# Buck.net
KiCad netlist of a schematic drawn in Altium Designer
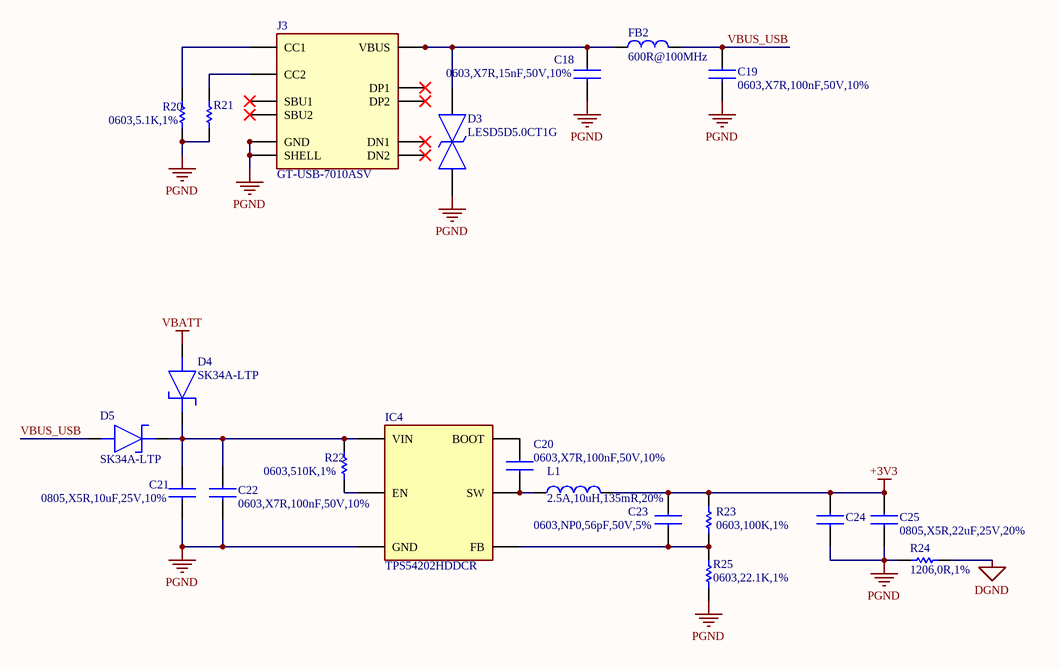
[diagram p0: Buck.SchDoc]

(export (version "E")
  (design (tool "Eeschema 10.0.6"))
  (components
    (comp (ref "C18")
      (value "0603,X7R,15nF,50V,10%")
      (footprint "CAPC1608X90N")
      (description "50V 15nF X7R ±10% 0603 Multilayer Ceramic Capacitors MLCC - SMD/SMT ROHS")
      (fields
        (field (name "MANUFACTURER_PART_NUMBER") "CC0603KRX7R9BB153")
        (field (name "MOUSER PART NUMBER") "603-CC603KRX7R9BB104")
      )
      (libsource (lib "ESC") (part "CC0603KRX7R9BB153"))
    )
    (comp (ref "C19")
      (value "0603,X7R,100nF,50V,10%")
      (footprint "CAPC1608X90N")
      (description "50V 100nF X7R ±10% 0603 Multilayer Ceramic Capacitors MLCC - SMD/SMT ROHS")
      (fields
        (field (name "MANUFACTURER_PART_NUMBER") "CC0603KRX7R9BB104")
        (field (name "MOUSER PART NUMBER") "603-CC603KRX7R9BB104")
      )
      (libsource (lib "ESC") (part "CC0603KRX7R9BB104"))
    )
    (comp (ref "C20")
      (value "0603,X7R,100nF,50V,10%")
      (footprint "CAPC1608X90N")
      (description "50V 100nF X7R ±10% 0603 Multilayer Ceramic Capacitors MLCC - SMD/SMT ROHS")
      (fields
        (field (name "MANUFACTURER_PART_NUMBER") "CC0603KRX7R9BB104")
        (field (name "MOUSER PART NUMBER") "603-CC603KRX7R9BB104")
      )
      (libsource (lib "ESC") (part "CC0603KRX7R9BB104"))
    )
    (comp (ref "C21")
      (value "0805,X5R,10uF,25V,10%")
      (footprint "CAPC2012X145N")
      (description "10 µF ±10% 25V Ceramic Capacitor X5R 0805 (2012 Metric)")
      (fields
        (field (name "MANUFACTURER_PART_NUMBER") "CC0805KKX5R8BB106")
        (field (name "MOUSER PART NUMBER") "603-CC805KKX5R8BB106")
      )
      (libsource (lib "ESC") (part "CC0805KKX5R8BB106"))
    )
    (comp (ref "C22")
      (value "0603,X7R,100nF,50V,10%")
      (footprint "CAPC1608X90N")
      (description "50V 100nF X7R ±10% 0603 Multilayer Ceramic Capacitors MLCC - SMD/SMT ROHS")
      (fields
        (field (name "MANUFACTURER_PART_NUMBER") "CC0603KRX7R9BB104")
        (field (name "MOUSER PART NUMBER") "603-CC603KRX7R9BB104")
      )
      (libsource (lib "ESC") (part "CC0603KRX7R9BB104"))
    )
    (comp (ref "C23")
      (value "0603,NP0,56pF,50V,5%")
      (footprint "CAPC1608X90N")
      (description "50V 56pF NP0 ±5% 0603 Ceramic Capacitors RoHS")
      (fields
        (field (name "MANUFACTURER_PART_NUMBER") "CC0603JRNPO9BN560")
        (field (name "MOUSER PART NUMBER") "603-CC603KRX7R9BB105")
      )
      (libsource (lib "ESC") (part "CC0603JRNPO9BN560"))
    )
    (comp (ref "C24")
      (value "0805,X5R,22uF,25V,20%")
      (footprint "CAPC2012X145N")
      (description "25V 22uF X5R ±20% 0805 Ceramic Capacitors RoHS")
      (fields
        (field (name "MANUFACTURER_PART_NUMBER") "CC0805MKX5R8BB226")
        (field (name "MOUSER PART NUMBER") "603-CC805KKX5R8BB106")
      )
      (libsource (lib "ESC") (part "CC0805MKX5R8BB226"))
    )
    (comp (ref "C25")
      (value "0805,X5R,22uF,25V,20%")
      (footprint "CAPC2012X145N")
      (description "25V 22uF X5R ±20% 0805 Ceramic Capacitors RoHS")
      (fields
        (field (name "MANUFACTURER_PART_NUMBER") "CC0805MKX5R8BB226")
        (field (name "MOUSER PART NUMBER") "603-CC805KKX5R8BB106")
      )
      (libsource (lib "ESC") (part "CC0805MKX5R8BB226"))
    )
    (comp (ref "D3")
      (value "LESD5D5.0CT1G")
      (footprint "LESD5D50CT1G")
      (description "9.4A 18.6V 5.6V Bidirectional 5V SOD-523 ESD and Surge Protection (TVS/ESD) ROHS")
      (fields (field (name "LCSC PART #") "C383211"))
      (libsource (lib "ESC") (part "LESD5D5.0CT1G"))
    )
    (comp (ref "D4")
      (value "SK34A-LTP")
      (footprint "SK34ALTP")
      (description "80A 40V 500mV@3A 3A SMA(DO-214AC) Single Diodes RoHS")
      (fields (field (name "MOUSER PART NUMBER") "833-SK34A-LTP") (field (name "LCSC PART #") "C85269"))
      (libsource (lib "ESC") (part "SK34A-LTP"))
    )
    (comp (ref "D5")
      (value "SK34A-LTP")
      (footprint "SK34ALTP")
      (description "80A 40V 500mV@3A 3A SMA(DO-214AC) Single Diodes RoHS")
      (fields (field (name "MOUSER PART NUMBER") "833-SK34A-LTP") (field (name "LCSC PART #") "C85269"))
      (libsource (lib "ESC") (part "SK34A-LTP"))
    )
    (comp (ref "FB2")
      (value "600R@100MHz")
      (footprint "L0603")
      (description "380mΩ ±25% 600Ω@100MHz 0603 Ferrite Beads ROHS")
      (fields (field (name "LCSC PART #") "C19330"))
      (libsource (lib "ESC") (part "BLM18AG601SN1D"))
    )
    (comp (ref "IC4")
      (value "TPS54202HDDCR")
      (footprint "SOT95P280X100-6N")
      (fields (field (name "MOUSER PART NUMBER") "595-TPS54202HDDCR") (field (name "LCSC PART #") "C527684"))
      (libsource (lib "ESC") (part "TPS54202HDDCR"))
    )
    (comp (ref "J3")
      (value "GT-USB-7010ASV")
      (footprint "USB-C-SMD_G-SWITCH_GT-USB-7010ASV")
      (description "USB 2.0 3A 1 Surface Mount, Right Angle 16P Female -40℃~+85℃ Type-C SMD USB Connectors ROHS")
      (fields (field (name "LCSC PART #") "C2988369"))
      (libsource (lib "ESC") (part "GT-USB-7010ASV"))
    )
    (comp (ref "L1")
      (value "2.5A,10uH,135mR,20%")
      (footprint "IND-SMD_L3.0-W3.0_FTC303020D")
      (description "2.5A 10uH ±20% 3.8A 135mΩ SMD,3x3mm Fixed Inductors RoHS")
      (fields (field (name "MANU PART #") "FTC303020D100MBCA") (field (name "LCSC PART #") "C7423323"))
      (libsource (lib "ESC") (part "FTC303020D100MBCA"))
    )
    (comp (ref "R20")
      (value "0603,5.1K,1%")
      (footprint "RESC1608X55N")
      (description "100mW 5.1kΩ 75V ±100ppm/℃ Thick Film Resistor ±1% 0603 Chip Resistor - Surface Mount RoHS")
      (fields
        (field (name "MANUFACTURER_PART_NUMBER") "RC0603FR-075K1L")
        (field (name "LCSC PART #") "C105580")
      )
      (libsource (lib "ESC") (part "RC0603FR-075K1L"))
    )
    (comp (ref "R21")
      (value "0603,5.1K,1%")
      (footprint "RESC1608X55N")
      (description "100mW 5.1kΩ 75V ±100ppm/℃ Thick Film Resistor ±1% 0603 Chip Resistor - Surface Mount RoHS")
      (fields
        (field (name "MANUFACTURER_PART_NUMBER") "RC0603FR-075K1L")
        (field (name "LCSC PART #") "C105580")
      )
      (libsource (lib "ESC") (part "RC0603FR-075K1L"))
    )
    (comp (ref "R22")
      (value "0603,510K,1%")
      (footprint "RESC1608X55N")
      (description "100mW 510kΩ 75V ±100ppm/℃ Thick Film Resistor ±1% 0603 Chip Resistor - Surface Mount RoHS")
      (fields
        (field (name "MANUFACTURER_PART_NUMBER") "RC0603FR-07510KL")
        (field (name "LCSC PART #") "C114066")
      )
      (libsource (lib "ESC") (part "RC0603FR-07510KL"))
    )
    (comp (ref "R23")
      (value "0603,100K,1%")
      (footprint "RESC1608X55N")
      (description "100mW Thick Film Resistor 75V ±100ppm/℃ ±1% 100kΩ 0603 Chip Resistor - Surface Mount ROHS")
      (fields
        (field (name "MANUFACTURER_PART_NUMBER") "RC0603FR-07100KL")
        (field (name "LCSC PART #") "C14675")
      )
      (libsource (lib "ESC") (part "RC0603FR-07100KL"))
    )
    (comp (ref "R24")
      (value "1206,0R,1%")
      (footprint "RESC3116X65N")
      (description "0Ω 250mW 200V Thick Film Resistor ±1% 1206 Chip Resistor - Surface Mount RoHS")
      (fields
        (field (name "MANUFACTURER_PART_NUMBER") "RC1206FR-070RL")
        (field (name "MOUSER PART NUMBER") "603-RC1206FR-070RL")
      )
      (libsource (lib "ESC") (part "RC1206FR-070RL"))
    )
    (comp (ref "R25")
      (value "0603,22.1K,1%")
      (footprint "RESC1608X55N")
      (description "22.1kΩ 100mW 75V ±100ppm/℃ Thick Film Resistor ±1% 0603 Chip Resistor - Surface Mount RoHS")
      (fields
        (field (name "MANUFACTURER_PART_NUMBER") "RC0603FR-0722K1L")
        (field (name "LCSC PART #") "C137768")
      )
      (libsource (lib "ESC") (part "RC0603FR-0722K1L"))
    )
  )
  (nets
    (net (code "1") (name "+3V3") (class "Default")
      (node (ref "C23") (pin "2") (pinfunction "2_2") (pintype "passive"))
      (node (ref "C24") (pin "2") (pinfunction "2_2") (pintype "passive"))
      (node (ref "C25") (pin "2") (pinfunction "2_2") (pintype "passive"))
      (node (ref "L1") (pin "2") (pinfunction "2_2") (pintype "passive"))
      (node (ref "R23") (pin "2") (pinfunction "2_2") (pintype "passive"))
    )
    (net (code "2") (name "/VBUS_USB") (class "Default")
      (node (ref "C19") (pin "2") (pinfunction "2_2") (pintype "passive"))
      (node (ref "D5") (pin "2") (pinfunction "A_2") (pintype "passive"))
      (node (ref "FB2") (pin "2") (pinfunction "2_2") (pintype "passive"))
    )
    (net (code "3") (name "DGND") (class "Default")
      (node (ref "R24") (pin "2") (pinfunction "2_2") (pintype "passive"))
    )
    (net (code "4") (name "Net-(C18-Pad2)") (class "Default")
      (node (ref "C18") (pin "2") (pinfunction "2_2") (pintype "passive"))
      (node (ref "D3") (pin "2") (pinfunction "2_2") (pintype "passive"))
      (node (ref "FB2") (pin "1") (pinfunction "1_1") (pintype "passive"))
      (node (ref "J3") (pin "A4B9") (pinfunction "VBUS_A4B9") (pintype "passive"))
      (node (ref "J3") (pin "B4A9") (pinfunction "VBUS_B4A9") (pintype "passive"))
    )
    (net (code "5") (name "Net-(D4-K)") (class "Default")
      (node (ref "C21") (pin "2") (pinfunction "2_2") (pintype "passive"))
      (node (ref "C22") (pin "2") (pinfunction "2_2") (pintype "passive"))
      (node (ref "D4") (pin "1") (pinfunction "K_1") (pintype "passive"))
      (node (ref "D5") (pin "1") (pinfunction "K_1") (pintype "passive"))
      (node (ref "IC4") (pin "3") (pinfunction "VIN_3") (pintype "passive"))
      (node (ref "R22") (pin "2") (pinfunction "2_2") (pintype "passive"))
    )
    (net (code "6") (name "Net-(IC4-BOOT)") (class "Default")
      (node (ref "C20") (pin "2") (pinfunction "2_2") (pintype "passive"))
      (node (ref "IC4") (pin "6") (pinfunction "BOOT_6") (pintype "passive"))
    )
    (net (code "7") (name "Net-(IC4-EN)") (class "Default")
      (node (ref "IC4") (pin "5") (pinfunction "EN_5") (pintype "passive"))
      (node (ref "R22") (pin "1") (pinfunction "1_1") (pintype "passive"))
    )
    (net (code "8") (name "Net-(IC4-FB)") (class "Default")
      (node (ref "C23") (pin "1") (pinfunction "1_1") (pintype "passive"))
      (node (ref "IC4") (pin "4") (pinfunction "FB_4") (pintype "passive"))
      (node (ref "R23") (pin "1") (pinfunction "1_1") (pintype "passive"))
      (node (ref "R25") (pin "2") (pinfunction "2_2") (pintype "passive"))
    )
    (net (code "9") (name "Net-(IC4-SW)") (class "Default")
      (node (ref "C20") (pin "1") (pinfunction "1_1") (pintype "passive"))
      (node (ref "IC4") (pin "2") (pinfunction "SW_2") (pintype "passive"))
      (node (ref "L1") (pin "1") (pinfunction "1_1") (pintype "passive"))
    )
    (net (code "10") (name "Net-(J3-CC1)") (class "Default")
      (node (ref "J3") (pin "A5") (pinfunction "CC1_A5") (pintype "passive"))
      (node (ref "R20") (pin "2") (pinfunction "2_2") (pintype "passive"))
    )
    (net (code "11") (name "Net-(J3-CC2)") (class "Default")
      (node (ref "J3") (pin "B5") (pinfunction "CC2_B5") (pintype "passive"))
      (node (ref "R21") (pin "2") (pinfunction "2_2") (pintype "passive"))
    )
    (net (code "12") (name "PGND") (class "Default")
      (node (ref "C18") (pin "1") (pinfunction "1_1") (pintype "passive"))
      (node (ref "C19") (pin "1") (pinfunction "1_1") (pintype "passive"))
      (node (ref "C21") (pin "1") (pinfunction "1_1") (pintype "passive"))
      (node (ref "C22") (pin "1") (pinfunction "1_1") (pintype "passive"))
      (node (ref "C24") (pin "1") (pinfunction "1_1") (pintype "passive"))
      (node (ref "C25") (pin "1") (pinfunction "1_1") (pintype "passive"))
      (node (ref "D3") (pin "1") (pinfunction "1_1") (pintype "passive"))
      (node (ref "IC4") (pin "1") (pinfunction "GND_1") (pintype "passive"))
      (node (ref "J3") (pin "1") (pinfunction "SHELL_1") (pintype "passive"))
      (node (ref "J3") (pin "2") (pinfunction "SHELL_2") (pintype "passive"))
      (node (ref "J3") (pin "3") (pinfunction "SHELL_3") (pintype "passive"))
      (node (ref "J3") (pin "4") (pinfunction "SHELL_4") (pintype "passive"))
      (node (ref "J3") (pin "A1B12") (pinfunction "GND_A1B12") (pintype "passive"))
      (node (ref "J3") (pin "B1A12") (pinfunction "GND_B1A12") (pintype "passive"))
      (node (ref "R20") (pin "1") (pinfunction "1_1") (pintype "passive"))
      (node (ref "R21") (pin "1") (pinfunction "1_1") (pintype "passive"))
      (node (ref "R24") (pin "1") (pinfunction "1_1") (pintype "passive"))
      (node (ref "R25") (pin "1") (pinfunction "1_1") (pintype "passive"))
    )
    (net (code "13") (name "VBATT") (class "Default")
      (node (ref "D4") (pin "2") (pinfunction "A_2") (pintype "passive"))
    )
    (net (code "14") (name "unconnected-(J3-DN1-PadA7)") (class "Default")
      (node (ref "J3") (pin "A7") (pinfunction "DN1_A7") (pintype "passive+no_connect"))
    )
    (net (code "15") (name "unconnected-(J3-DN2-PadB7)") (class "Default")
      (node (ref "J3") (pin "B7") (pinfunction "DN2_B7") (pintype "passive+no_connect"))
    )
    (net (code "16") (name "unconnected-(J3-DP1-PadA6)") (class "Default")
      (node (ref "J3") (pin "A6") (pinfunction "DP1_A6") (pintype "passive+no_connect"))
    )
    (net (code "17") (name "unconnected-(J3-DP2-PadB6)") (class "Default")
      (node (ref "J3") (pin "B6") (pinfunction "DP2_B6") (pintype "passive+no_connect"))
    )
    (net (code "18") (name "unconnected-(J3-SBU1-PadA8)") (class "Default")
      (node (ref "J3") (pin "A8") (pinfunction "SBU1_A8") (pintype "passive+no_connect"))
    )
    (net (code "19") (name "unconnected-(J3-SBU2-PadB8)") (class "Default")
      (node (ref "J3") (pin "B8") (pinfunction "SBU2_B8") (pintype "passive+no_connect"))
    )
  )
)
